# underground_cable_fault_finder.net
KiCad netlist of a schematic drawn in EAGLE
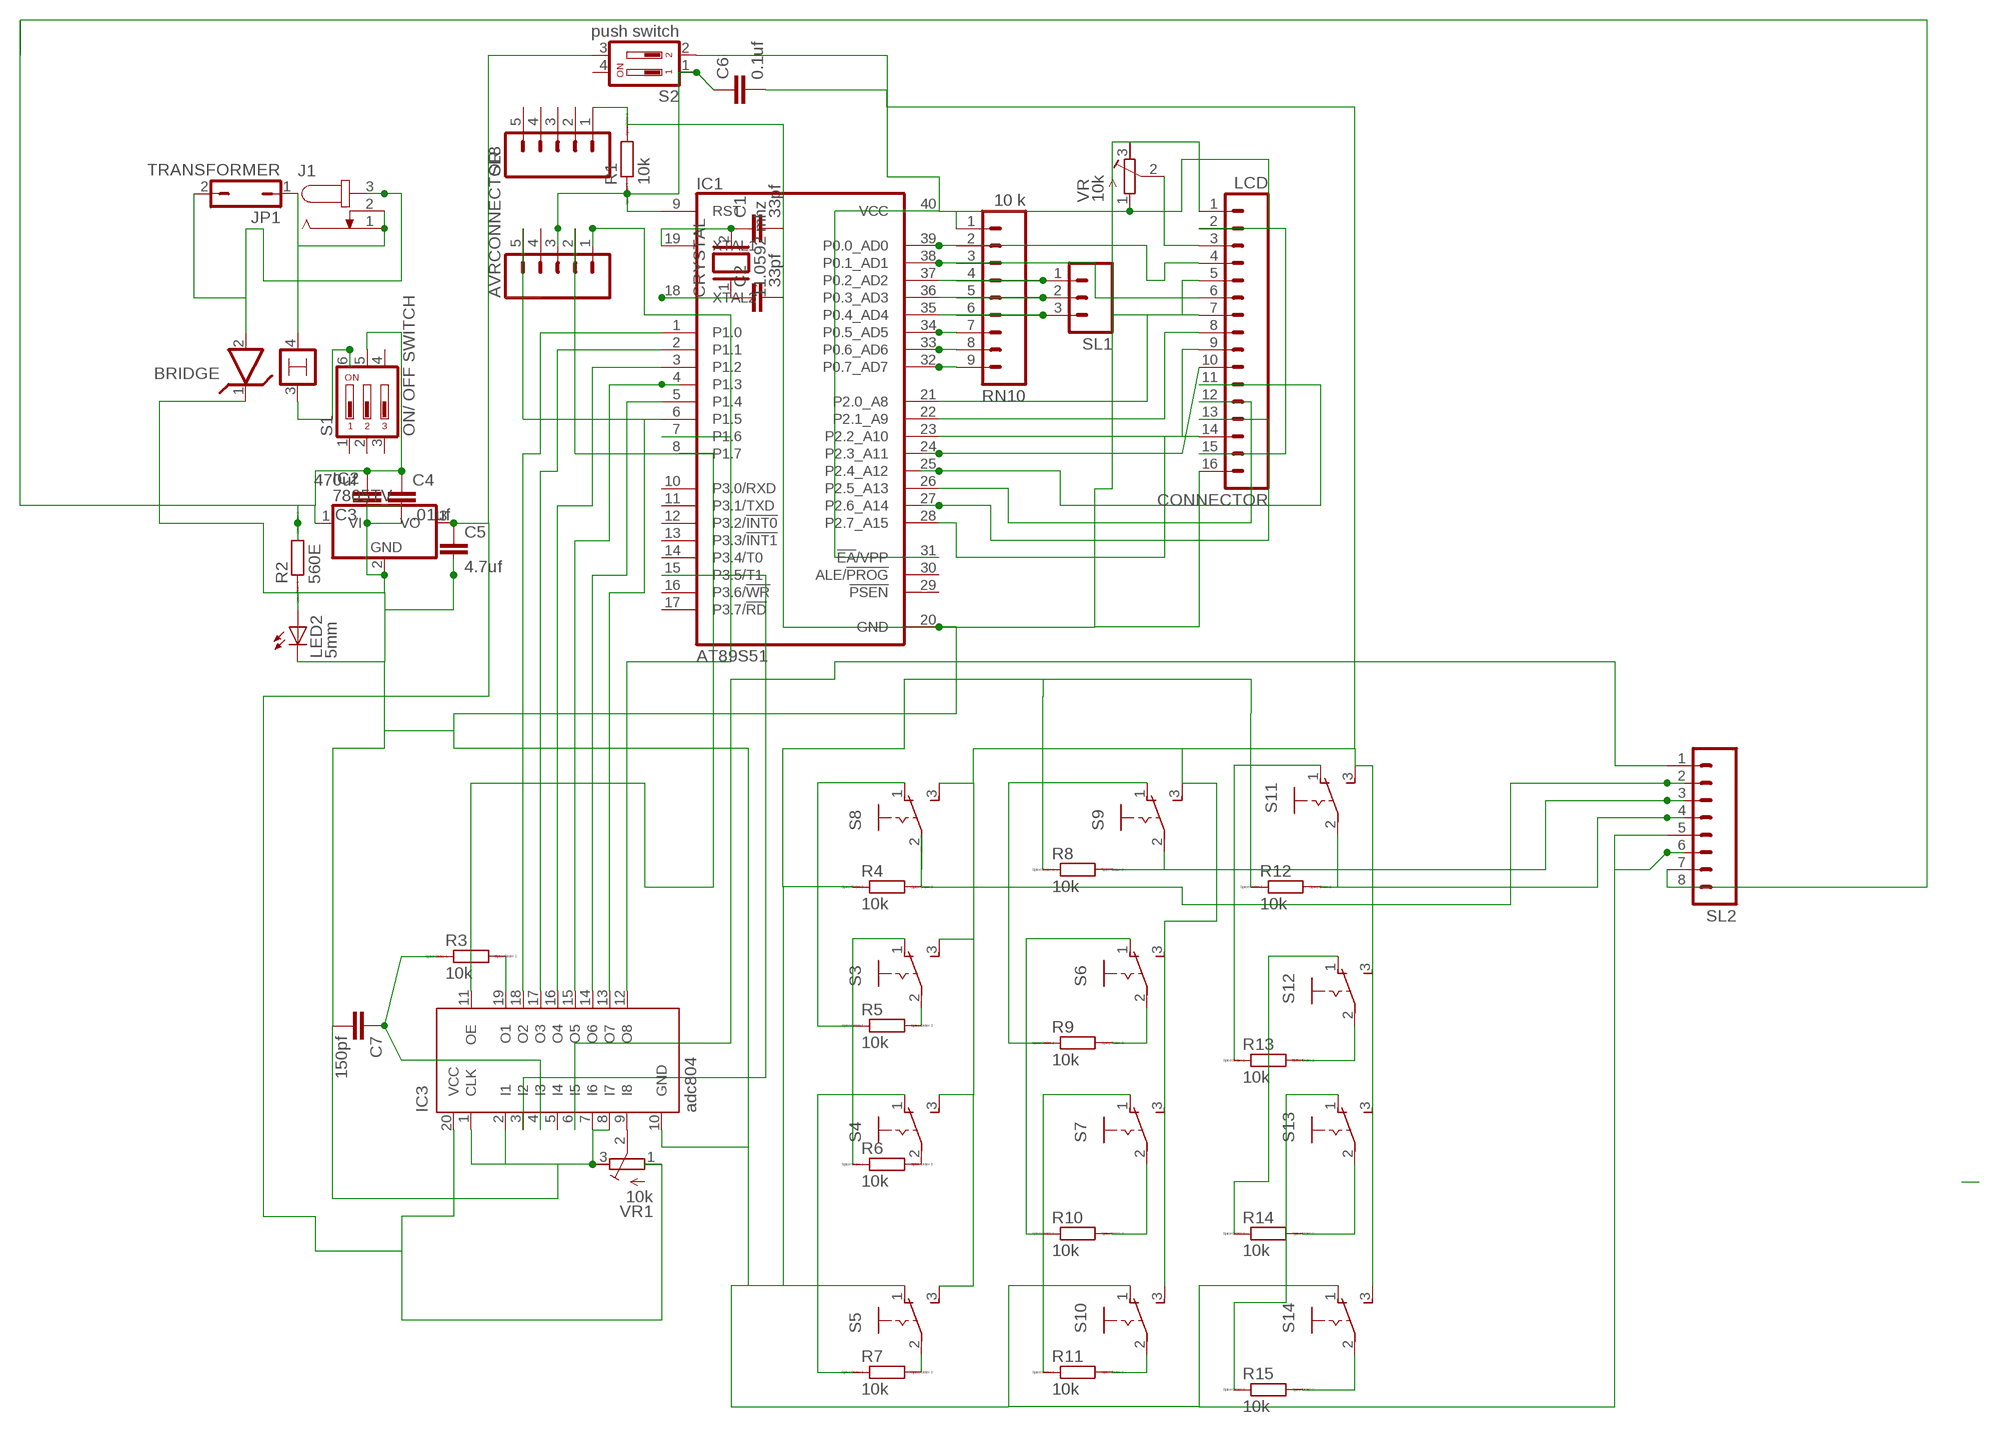
[diagram p0: schematic, sheet 1]

(export (version "E")
  (design (tool "Eeschema 10.0.6"))
  (components
    (comp (ref "AVRCONNECTOR")
      (value "M05")
      (footprint "eagle-import:05P")
      (libsource (lib "eagle-import") (part "M05"))
    )
    (comp (ref "BRIDGE")
      (value "LM399H")
      (footprint "eagle-import:TO39_4")
      (libsource (lib "eagle-import") (part "LM399H"))
    )
    (comp (ref "C1")
      (value "33pf")
      (footprint "eagle-import:C025-024X044")
      (libsource (lib "eagle-import") (part "C-EU025-024X044"))
    )
    (comp (ref "C2")
      (value "33pf")
      (footprint "eagle-import:C025-024X044")
      (libsource (lib "eagle-import") (part "C-EU025-024X044"))
    )
    (comp (ref "C3")
      (value "470uf")
      (footprint "eagle-import:C5B7.2")
      (libsource (lib "eagle-import") (part "C5/7.2"))
    )
    (comp (ref "C4")
      (value ".01uf")
      (footprint "eagle-import:C2.5-3")
      (libsource (lib "eagle-import") (part "C2,5-3"))
    )
    (comp (ref "C5")
      (value "4.7uf")
      (footprint "eagle-import:C2.5-3")
      (libsource (lib "eagle-import") (part "C2,5-3"))
    )
    (comp (ref "C6")
      (value "0.1uf")
      (footprint "eagle-import:C2.5-6")
      (libsource (lib "eagle-import") (part "C2.5/6"))
    )
    (comp (ref "C7")
      (value "150pf")
      (footprint "eagle-import:C2.5-3")
      (libsource (lib "eagle-import") (part "C2,5-3"))
    )
    (comp (ref "CONNECTOR")
      (value "LCD")
      (footprint "eagle-import:16P")
      (libsource (lib "eagle-import") (part "M16"))
    )
    (comp (ref "CRYSTAL")
      (value "11.0592 mhz")
      (footprint "eagle-import:QS")
      (libsource (lib "eagle-import") (part "XTAL/S"))
    )
    (comp (ref "IC1")
      (value "AT89S51")
      (footprint "eagle-import:DIL40")
      (libsource (lib "eagle-import") (part "AT89C51-PC12"))
    )
    (comp (ref "IC2")
      (value "7805TV")
      (footprint "eagle-import:TO220V")
      (libsource (lib "eagle-import") (part "78TV05"))
    )
    (comp (ref "IC3")
      (value "adc804")
      (footprint "eagle-import:DIL20")
      (fields (field (name "MPN") "ATF16V8CZ-15PU"))
      (libsource (lib "eagle-import") (part "ATF16V8BP3"))
    )
    (comp (ref "J1")
      (value "JACK-PLUG0")
      (footprint "eagle-import:SPC4077")
      (libsource (lib "eagle-import") (part "JACK-PLUG0"))
    )
    (comp (ref "JP1")
      (value "TRANSFORMER")
      (footprint "eagle-import:JP1")
      (libsource (lib "eagle-import") (part "JP1Q"))
    )
    (comp (ref "LED2")
      (value "5mm")
      (footprint "eagle-import:LED5MM")
      (libsource (lib "eagle-import") (part "LED5MM"))
    )
    (comp (ref "R1")
      (value "10k")
      (footprint "eagle-import:0204_7")
      (libsource (lib "eagle-import") (part "R0204/7"))
    )
    (comp (ref "R2")
      (value "560E")
      (footprint "eagle-import:0204_7")
      (libsource (lib "eagle-import") (part "R0204/7"))
    )
    (comp (ref "R3")
      (value "10k")
      (footprint "eagle-import:0204_7")
      (libsource (lib "eagle-import") (part "R0204/7"))
    )
    (comp (ref "R4")
      (value "10k")
      (footprint "eagle-import:0204_7")
      (fields (field (name "SPICEMODEL") "NONE") (field (name "SPICEPREFIX") "R"))
      (libsource (lib "eagle-import") (part "R0204/7"))
    )
    (comp (ref "R5")
      (value "10k")
      (footprint "eagle-import:0204_7")
      (fields (field (name "SPICEMODEL") "NONE") (field (name "SPICEPREFIX") "R"))
      (libsource (lib "eagle-import") (part "R0204/7"))
    )
    (comp (ref "R6")
      (value "10k")
      (footprint "eagle-import:0204_7")
      (fields (field (name "SPICEMODEL") "NONE") (field (name "SPICEPREFIX") "R"))
      (libsource (lib "eagle-import") (part "R0204/7"))
    )
    (comp (ref "R7")
      (value "10k")
      (footprint "eagle-import:0204_7")
      (fields (field (name "SPICEMODEL") "NONE") (field (name "SPICEPREFIX") "R"))
      (libsource (lib "eagle-import") (part "R0204/7"))
    )
    (comp (ref "R8")
      (value "10k")
      (footprint "eagle-import:0204_7")
      (fields (field (name "SPICEMODEL") "NONE") (field (name "SPICEPREFIX") "R"))
      (libsource (lib "eagle-import") (part "R0204/7"))
    )
    (comp (ref "R9")
      (value "10k")
      (footprint "eagle-import:0204_7")
      (fields (field (name "SPICEMODEL") "NONE") (field (name "SPICEPREFIX") "R"))
      (libsource (lib "eagle-import") (part "R0204/7"))
    )
    (comp (ref "R10")
      (value "10k")
      (footprint "eagle-import:0204_7")
      (fields (field (name "SPICEMODEL") "NONE") (field (name "SPICEPREFIX") "R"))
      (libsource (lib "eagle-import") (part "R0204/7"))
    )
    (comp (ref "R11")
      (value "10k")
      (footprint "eagle-import:0204_7")
      (fields (field (name "SPICEMODEL") "NONE") (field (name "SPICEPREFIX") "R"))
      (libsource (lib "eagle-import") (part "R0204/7"))
    )
    (comp (ref "R12")
      (value "10k")
      (footprint "eagle-import:0204_7")
      (fields (field (name "SPICEMODEL") "NONE") (field (name "SPICEPREFIX") "R"))
      (libsource (lib "eagle-import") (part "R0204/7"))
    )
    (comp (ref "R13")
      (value "10k")
      (footprint "eagle-import:0204_7")
      (fields (field (name "SPICEMODEL") "NONE") (field (name "SPICEPREFIX") "R"))
      (libsource (lib "eagle-import") (part "R0204/7"))
    )
    (comp (ref "R14")
      (value "10k")
      (footprint "eagle-import:0204_7")
      (fields (field (name "SPICEMODEL") "NONE") (field (name "SPICEPREFIX") "R"))
      (libsource (lib "eagle-import") (part "R0204/7"))
    )
    (comp (ref "R15")
      (value "10k")
      (footprint "eagle-import:0204_7")
      (fields (field (name "SPICEMODEL") "NONE") (field (name "SPICEPREFIX") "R"))
      (libsource (lib "eagle-import") (part "R0204/7"))
    )
    (comp (ref "RN10")
      (value "10 k")
      (footprint "eagle-import:09P")
      (libsource (lib "eagle-import") (part "M09"))
    )
    (comp (ref "S1")
      (value "ON/ OFF SWITCH")
      (footprint "eagle-import:DA-03")
      (fields (field (name "MPN") "MCDA03"))
      (libsource (lib "eagle-import") (part "DA03"))
    )
    (comp (ref "S2")
      (value "push switch")
      (footprint "eagle-import:DP-02")
      (fields (field (name "MPN") "MCDP02"))
      (libsource (lib "eagle-import") (part "DP02"))
    )
    (comp (ref "S3")
      (value "255SB")
      (footprint "eagle-import:255SB")
      (libsource (lib "eagle-import") (part "255SB"))
    )
    (comp (ref "S4")
      (value "255SB")
      (footprint "eagle-import:255SB")
      (libsource (lib "eagle-import") (part "255SB"))
    )
    (comp (ref "S5")
      (value "255SB")
      (footprint "eagle-import:255SB")
      (libsource (lib "eagle-import") (part "255SB"))
    )
    (comp (ref "S6")
      (value "255SB")
      (footprint "eagle-import:255SB")
      (libsource (lib "eagle-import") (part "255SB"))
    )
    (comp (ref "S7")
      (value "255SB")
      (footprint "eagle-import:255SB")
      (libsource (lib "eagle-import") (part "255SB"))
    )
    (comp (ref "S8")
      (value "255SB")
      (footprint "eagle-import:255SB")
      (libsource (lib "eagle-import") (part "255SB"))
    )
    (comp (ref "S9")
      (value "255SB")
      (footprint "eagle-import:255SB")
      (libsource (lib "eagle-import") (part "255SB"))
    )
    (comp (ref "S10")
      (value "255SB")
      (footprint "eagle-import:255SB")
      (libsource (lib "eagle-import") (part "255SB"))
    )
    (comp (ref "S11")
      (value "255SB")
      (footprint "eagle-import:255SB")
      (libsource (lib "eagle-import") (part "255SB"))
    )
    (comp (ref "S12")
      (value "255SB")
      (footprint "eagle-import:255SB")
      (libsource (lib "eagle-import") (part "255SB"))
    )
    (comp (ref "S13")
      (value "255SB")
      (footprint "eagle-import:255SB")
      (libsource (lib "eagle-import") (part "255SB"))
    )
    (comp (ref "S14")
      (value "255SB")
      (footprint "eagle-import:255SB")
      (libsource (lib "eagle-import") (part "255SB"))
    )
    (comp (ref "SL1")
      (value "M03")
      (footprint "eagle-import:03P")
      (libsource (lib "eagle-import") (part "M03"))
    )
    (comp (ref "SL2")
      (value "M08")
      (footprint "eagle-import:08P")
      (libsource (lib "eagle-import") (part "M08"))
    )
    (comp (ref "SL8")
      (value "M05")
      (footprint "eagle-import:05P")
      (libsource (lib "eagle-import") (part "M05"))
    )
    (comp (ref "VR")
      (value "10k")
      (footprint "eagle-import:RTRIM64P")
      (libsource (lib "eagle-import") (part "R-TRIMM64P"))
    )
    (comp (ref "VR1")
      (value "10k")
      (footprint "eagle-import:RTRIM64P")
      (libsource (lib "eagle-import") (part "R-TRIMM64P"))
    )
  )
  (nets
    (net (code "1") (name "Net-(BRIDGE-Pad2)") (class "Default")
      (node (ref "BRIDGE") (pin "2") (pinfunction "2_2") (pintype "input"))
      (node (ref "J1") (pin "3") (pinfunction "3_3") (pintype "passive"))
      (node (ref "JP1") (pin "2") (pinfunction "2_2") (pintype "passive"))
    )
    (net (code "2") (name "Net-(BRIDGE-Pad3)") (class "Default")
      (node (ref "BRIDGE") (pin "3") (pinfunction "3_3") (pintype "input"))
      (node (ref "S1") (pin "6") (pinfunction "6_6") (pintype "passive"))
    )
    (net (code "3") (name "Net-(BRIDGE-Pad4)") (class "Default")
      (node (ref "BRIDGE") (pin "4") (pinfunction "4_4") (pintype "input"))
      (node (ref "J1") (pin "1") (pinfunction "1_1") (pintype "passive"))
      (node (ref "J1") (pin "2") (pinfunction "2_2") (pintype "passive"))
      (node (ref "JP1") (pin "1") (pinfunction "1_1") (pintype "passive"))
    )
    (net (code "4") (name "Net-(IC1-GND)") (class "Default")
      (node (ref "BRIDGE") (pin "1") (pinfunction "1_1") (pintype "input"))
      (node (ref "C1") (pin "2") (pinfunction "2_2") (pintype "passive"))
      (node (ref "C2") (pin "2") (pinfunction "2_2") (pintype "passive"))
      (node (ref "C3") (pin "1") (pinfunction "1_1") (pintype "passive"))
      (node (ref "C4") (pin "2") (pinfunction "2_2") (pintype "passive"))
      (node (ref "C5") (pin "2") (pinfunction "2_2") (pintype "passive"))
      (node (ref "C7") (pin "2") (pinfunction "2_2") (pintype "passive"))
      (node (ref "CONNECTOR") (pin "1") (pinfunction "1_1") (pintype "passive"))
      (node (ref "CONNECTOR") (pin "16") (pinfunction "16_16") (pintype "passive"))
      (node (ref "CONNECTOR") (pin "5") (pinfunction "5_5") (pintype "passive"))
      (node (ref "IC1") (pin "20") (pinfunction "GND_20") (pintype "power_in"))
      (node (ref "IC2") (pin "2") (pinfunction "GND_2") (pintype "passive"))
      (node (ref "IC3") (pin "1") (pinfunction "CLK_1") (pintype "input"))
      (node (ref "IC3") (pin "10") (pinfunction "GND_10") (pintype "power_in"))
      (node (ref "IC3") (pin "2") (pinfunction "I1_2") (pintype "input"))
      (node (ref "IC3") (pin "7") (pinfunction "I6_7") (pintype "input"))
      (node (ref "IC3") (pin "8") (pinfunction "I7_8") (pintype "input"))
      (node (ref "LED2") (pin "K") (pinfunction "C_K") (pintype "passive"))
      (node (ref "R1") (pin "2") (pinfunction "2_2") (pintype "passive"))
      (node (ref "R12") (pin "1") (pinfunction "1_1") (pintype "passive"))
      (node (ref "R4") (pin "1") (pinfunction "1_1") (pintype "passive"))
      (node (ref "R8") (pin "1") (pinfunction "1_1") (pintype "passive"))
      (node (ref "S10") (pin "1") (pinfunction "O_1") (pintype "passive"))
      (node (ref "S14") (pin "1") (pinfunction "O_1") (pintype "passive"))
      (node (ref "S5") (pin "1") (pinfunction "O_1") (pintype "passive"))
      (node (ref "SL2") (pin "5") (pinfunction "5_5") (pintype "passive"))
      (node (ref "SL2") (pin "6") (pinfunction "6_6") (pintype "passive"))
      (node (ref "SL8") (pin "1") (pinfunction "1_1") (pintype "passive"))
      (node (ref "VR") (pin "3") (pinfunction "A_3") (pintype "passive"))
      (node (ref "VR1") (pin "3") (pinfunction "A_3") (pintype "passive"))
    )
    (net (code "5") (name "Net-(IC1-P0.0_AD0)") (class "Default")
      (node (ref "CONNECTOR") (pin "4") (pinfunction "4_4") (pintype "passive"))
      (node (ref "IC1") (pin "39") (pinfunction "P0.0_AD0_39") (pintype "bidirectional"))
      (node (ref "RN10") (pin "2") (pinfunction "2_2") (pintype "passive"))
    )
    (net (code "6") (name "Net-(IC1-P0.1_AD1)") (class "Default")
      (node (ref "CONNECTOR") (pin "6") (pinfunction "6_6") (pintype "passive"))
      (node (ref "IC1") (pin "38") (pinfunction "P0.1_AD1_38") (pintype "bidirectional"))
      (node (ref "RN10") (pin "3") (pinfunction "3_3") (pintype "passive"))
    )
    (net (code "7") (name "Net-(IC1-P0.2_AD2)") (class "Default")
      (node (ref "IC1") (pin "37") (pinfunction "P0.2_AD2_37") (pintype "bidirectional"))
      (node (ref "RN10") (pin "4") (pinfunction "4_4") (pintype "passive"))
      (node (ref "SL1") (pin "1") (pinfunction "1_1") (pintype "passive"))
    )
    (net (code "8") (name "Net-(IC1-P0.3_AD3)") (class "Default")
      (node (ref "IC1") (pin "36") (pinfunction "P0.3_AD3_36") (pintype "bidirectional"))
      (node (ref "RN10") (pin "5") (pinfunction "5_5") (pintype "passive"))
      (node (ref "SL1") (pin "2") (pinfunction "2_2") (pintype "passive"))
    )
    (net (code "9") (name "Net-(IC1-P0.4_AD4)") (class "Default")
      (node (ref "IC1") (pin "35") (pinfunction "P0.4_AD4_35") (pintype "bidirectional"))
      (node (ref "RN10") (pin "6") (pinfunction "6_6") (pintype "passive"))
      (node (ref "SL1") (pin "3") (pinfunction "3_3") (pintype "passive"))
    )
    (net (code "10") (name "Net-(IC1-P0.5_AD5)") (class "Default")
      (node (ref "IC1") (pin "34") (pinfunction "P0.5_AD5_34") (pintype "bidirectional"))
      (node (ref "RN10") (pin "7") (pinfunction "7_7") (pintype "passive"))
    )
    (net (code "11") (name "Net-(IC1-P0.6_AD6)") (class "Default")
      (node (ref "IC1") (pin "33") (pinfunction "P0.6_AD6_33") (pintype "bidirectional"))
      (node (ref "RN10") (pin "8") (pinfunction "8_8") (pintype "passive"))
    )
    (net (code "12") (name "Net-(IC1-P0.7_AD7)") (class "Default")
      (node (ref "IC1") (pin "32") (pinfunction "P0.7_AD7_32") (pintype "bidirectional"))
      (node (ref "RN10") (pin "9") (pinfunction "9_9") (pintype "passive"))
    )
    (net (code "13") (name "Net-(IC1-P1.0)") (class "Default")
      (node (ref "IC1") (pin "1") (pinfunction "P1.0_1") (pintype "bidirectional"))
      (node (ref "IC3") (pin "18") (pinfunction "O2_18") (pintype "output"))
    )
    (net (code "14") (name "Net-(IC1-P1.1)") (class "Default")
      (node (ref "IC1") (pin "2") (pinfunction "P1.1_2") (pintype "bidirectional"))
      (node (ref "IC3") (pin "17") (pinfunction "O3_17") (pintype "output"))
    )
    (net (code "15") (name "Net-(IC1-P1.2)") (class "Default")
      (node (ref "IC1") (pin "3") (pinfunction "P1.2_3") (pintype "bidirectional"))
      (node (ref "IC3") (pin "16") (pinfunction "O4_16") (pintype "output"))
    )
    (net (code "16") (name "Net-(IC1-P1.3)") (class "Default")
      (node (ref "IC1") (pin "4") (pinfunction "P1.3_4") (pintype "bidirectional"))
      (node (ref "IC3") (pin "15") (pinfunction "O5_15") (pintype "output"))
    )
    (net (code "17") (name "Net-(IC1-P1.4)") (class "Default")
      (node (ref "IC1") (pin "5") (pinfunction "P1.4_5") (pintype "bidirectional"))
      (node (ref "IC3") (pin "14") (pinfunction "O6_14") (pintype "output"))
    )
    (net (code "18") (name "Net-(IC1-P1.5)") (class "Default")
      (node (ref "AVRCONNECTOR") (pin "5") (pinfunction "5_5") (pintype "passive"))
      (node (ref "IC1") (pin "6") (pinfunction "P1.5_6") (pintype "bidirectional"))
      (node (ref "IC3") (pin "13") (pinfunction "O7_13") (pintype "output"))
    )
    (net (code "19") (name "Net-(IC1-P1.6)") (class "Default")
      (node (ref "AVRCONNECTOR") (pin "1") (pinfunction "1_1") (pintype "passive"))
      (node (ref "IC1") (pin "7") (pinfunction "P1.6_7") (pintype "bidirectional"))
      (node (ref "IC3") (pin "12") (pinfunction "O8_12") (pintype "output"))
    )
    (net (code "20") (name "Net-(IC1-P1.7)") (class "Default")
      (node (ref "AVRCONNECTOR") (pin "2") (pinfunction "2_2") (pintype "passive"))
      (node (ref "IC1") (pin "8") (pinfunction "P1.7_8") (pintype "bidirectional"))
      (node (ref "IC3") (pin "11") (pinfunction "OE_11") (pintype "input"))
    )
    (net (code "21") (name "Net-(IC1-P2.0_A8)") (class "Default")
      (node (ref "CONNECTOR") (pin "7") (pinfunction "7_7") (pintype "passive"))
      (node (ref "IC1") (pin "21") (pinfunction "P2.0_A8_21") (pintype "bidirectional"))
    )
    (net (code "22") (name "Net-(IC1-P2.1_A9)") (class "Default")
      (node (ref "CONNECTOR") (pin "8") (pinfunction "8_8") (pintype "passive"))
      (node (ref "IC1") (pin "22") (pinfunction "P2.1_A9_22") (pintype "bidirectional"))
    )
    (net (code "23") (name "Net-(IC1-P2.2_A10)") (class "Default")
      (node (ref "CONNECTOR") (pin "9") (pinfunction "9_9") (pintype "passive"))
      (node (ref "IC1") (pin "23") (pinfunction "P2.2_A10_23") (pintype "bidirectional"))
    )
    (net (code "24") (name "Net-(IC1-P2.3_A11)") (class "Default")
      (node (ref "CONNECTOR") (pin "10") (pinfunction "10_10") (pintype "passive"))
      (node (ref "IC1") (pin "24") (pinfunction "P2.3_A11_24") (pintype "bidirectional"))
    )
    (net (code "25") (name "Net-(IC1-P2.4_A12)") (class "Default")
      (node (ref "CONNECTOR") (pin "11") (pinfunction "11_11") (pintype "passive"))
      (node (ref "IC1") (pin "25") (pinfunction "P2.4_A12_25") (pintype "bidirectional"))
    )
    (net (code "26") (name "Net-(IC1-P2.5_A13)") (class "Default")
      (node (ref "CONNECTOR") (pin "12") (pinfunction "12_12") (pintype "passive"))
      (node (ref "IC1") (pin "26") (pinfunction "P2.5_A13_26") (pintype "bidirectional"))
    )
    (net (code "27") (name "Net-(IC1-P2.6_A14)") (class "Default")
      (node (ref "CONNECTOR") (pin "13") (pinfunction "13_13") (pintype "passive"))
      (node (ref "IC1") (pin "27") (pinfunction "P2.6_A14_27") (pintype "bidirectional"))
    )
    (net (code "28") (name "Net-(IC1-P2.7_A15)") (class "Default")
      (node (ref "CONNECTOR") (pin "14") (pinfunction "14_14") (pintype "passive"))
      (node (ref "IC1") (pin "28") (pinfunction "P2.7_A15_28") (pintype "bidirectional"))
    )
    (net (code "29") (name "Net-(IC1-P3.5{slash}T1)") (class "Default")
      (node (ref "IC1") (pin "15") (pinfunction "P3.5/T1_15") (pintype "bidirectional"))
      (node (ref "IC3") (pin "3") (pinfunction "I2_3") (pintype "input"))
    )
    (net (code "30") (name "Net-(IC1-RST)") (class "Default")
      (node (ref "AVRCONNECTOR") (pin "3") (pinfunction "3_3") (pintype "passive"))
      (node (ref "C6") (pin "1") (pinfunction "1_1") (pintype "passive"))
      (node (ref "IC1") (pin "9") (pinfunction "RST_9") (pintype "input"))
      (node (ref "R1") (pin "1") (pinfunction "1_1") (pintype "passive"))
      (node (ref "S2") (pin "1") (pinfunction "1_1") (pintype "passive"))
    )
    (net (code "31") (name "Net-(IC1-VCC)") (class "Default")
      (node (ref "C6") (pin "2") (pinfunction "2_2") (pintype "passive"))
      (node (ref "CONNECTOR") (pin "15") (pinfunction "15_15") (pintype "passive"))
      (node (ref "CONNECTOR") (pin "2") (pinfunction "2_2") (pintype "passive"))
      (node (ref "IC1") (pin "31") (pinfunction "~{EA}/VPP_31") (pintype "input"))
      (node (ref "IC1") (pin "40") (pinfunction "VCC_40") (pintype "power_in"))
      (node (ref "RN10") (pin "1") (pinfunction "1_1") (pintype "passive"))
      (node (ref "S10") (pin "3") (pinfunction "S_3") (pintype "passive"))
      (node (ref "S11") (pin "3") (pinfunction "S_3") (pintype "passive"))
      (node (ref "S12") (pin "3") (pinfunction "S_3") (pintype "passive"))
      (node (ref "S13") (pin "3") (pinfunction "S_3") (pintype "passive"))
      (node (ref "S14") (pin "3") (pinfunction "S_3") (pintype "passive"))
      (node (ref "S2") (pin "2") (pinfunction "2_2") (pintype "passive"))
      (node (ref "S3") (pin "3") (pinfunction "S_3") (pintype "passive"))
      (node (ref "S4") (pin "3") (pinfunction "S_3") (pintype "passive"))
      (node (ref "S5") (pin "3") (pinfunction "S_3") (pintype "passive"))
      (node (ref "S6") (pin "3") (pinfunction "S_3") (pintype "passive"))
      (node (ref "S7") (pin "3") (pinfunction "S_3") (pintype "passive"))
      (node (ref "S8") (pin "3") (pinfunction "S_3") (pintype "passive"))
      (node (ref "S9") (pin "3") (pinfunction "S_3") (pintype "passive"))
      (node (ref "VR") (pin "1") (pinfunction "E_1") (pintype "passive"))
    )
    (net (code "32") (name "Net-(IC1-XTAL1)") (class "Default")
      (node (ref "C1") (pin "1") (pinfunction "1_1") (pintype "passive"))
      (node (ref "CRYSTAL") (pin "2") (pinfunction "2_2") (pintype "passive"))
      (node (ref "IC1") (pin "19") (pinfunction "XTAL1_19") (pintype "input"))
    )
    (net (code "33") (name "Net-(IC1-XTAL2)") (class "Default")
      (node (ref "C2") (pin "1") (pinfunction "1_1") (pintype "passive"))
      (node (ref "CRYSTAL") (pin "1") (pinfunction "1_1") (pintype "passive"))
      (node (ref "IC1") (pin "18") (pinfunction "XTAL2_18") (pintype "input"))
    )
    (net (code "34") (name "Net-(IC2-VI)") (class "Default")
      (node (ref "C3") (pin "2") (pinfunction "2_2") (pintype "passive"))
      (node (ref "C4") (pin "1") (pinfunction "1_1") (pintype "passive"))
      (node (ref "IC2") (pin "1") (pinfunction "VI_1") (pintype "input"))
      (node (ref "R2") (pin "2") (pinfunction "2_2") (pintype "passive"))
      (node (ref "S1") (pin "5") (pinfunction "5_5") (pintype "passive"))
      (node (ref "SL2") (pin "7") (pinfunction "7_7") (pintype "passive"))
      (node (ref "SL2") (pin "8") (pinfunction "8_8") (pintype "passive"))
    )
    (net (code "35") (name "Net-(IC2-VO)") (class "Default")
      (node (ref "C5") (pin "1") (pinfunction "1_1") (pintype "passive"))
      (node (ref "IC2") (pin "3") (pinfunction "VO_3") (pintype "passive"))
      (node (ref "IC3") (pin "20") (pinfunction "VCC_20") (pintype "power_in"))
      (node (ref "S2") (pin "3") (pinfunction "3_3") (pintype "passive"))
      (node (ref "VR1") (pin "1") (pinfunction "E_1") (pintype "passive"))
    )
    (net (code "36") (name "Net-(IC3-I3)") (class "Default")
      (node (ref "C7") (pin "1") (pinfunction "1_1") (pintype "passive"))
      (node (ref "IC3") (pin "4") (pinfunction "I3_4") (pintype "input"))
      (node (ref "R3") (pin "1") (pinfunction "1_1") (pintype "passive"))
    )
    (net (code "37") (name "Net-(IC3-I5)") (class "Default")
      (node (ref "IC3") (pin "6") (pinfunction "I5_6") (pintype "input"))
      (node (ref "SL2") (pin "1") (pinfunction "1_1") (pintype "passive"))
    )
    (net (code "38") (name "Net-(IC3-I8)") (class "Default")
      (node (ref "IC3") (pin "9") (pinfunction "I8_9") (pintype "input"))
      (node (ref "VR1") (pin "2") (pinfunction "S_2") (pintype "passive"))
    )
    (net (code "39") (name "Net-(IC3-O1)") (class "Default")
      (node (ref "IC3") (pin "19") (pinfunction "O1_19") (pintype "output"))
      (node (ref "R3") (pin "2") (pinfunction "2_2") (pintype "passive"))
    )
    (net (code "40") (name "Net-(LED2-PadA)") (class "Default")
      (node (ref "LED2") (pin "A") (pinfunction "A_A") (pintype "passive"))
      (node (ref "R2") (pin "1") (pinfunction "1_1") (pintype "passive"))
    )
    (net (code "41") (name "Net-(S3-O)") (class "Default")
      (node (ref "R6") (pin "1") (pinfunction "1_1") (pintype "passive"))
      (node (ref "S3") (pin "1") (pinfunction "O_1") (pintype "passive"))
    )
    (net (code "42") (name "Net-(S3-P)") (class "Default")
      (node (ref "R5") (pin "2") (pinfunction "2_2") (pintype "passive"))
      (node (ref "S3") (pin "2") (pinfunction "P_2") (pintype "passive"))
    )
    (net (code "43") (name "Net-(S4-O)") (class "Default")
      (node (ref "R7") (pin "1") (pinfunction "1_1") (pintype "passive"))
      (node (ref "S4") (pin "1") (pinfunction "O_1") (pintype "passive"))
    )
    (net (code "44") (name "Net-(S4-P)") (class "Default")
      (node (ref "R6") (pin "2") (pinfunction "2_2") (pintype "passive"))
      (node (ref "S4") (pin "2") (pinfunction "P_2") (pintype "passive"))
    )
    (net (code "45") (name "Net-(S5-P)") (class "Default")
      (node (ref "R7") (pin "2") (pinfunction "2_2") (pintype "passive"))
      (node (ref "S5") (pin "2") (pinfunction "P_2") (pintype "passive"))
    )
    (net (code "46") (name "Net-(S6-O)") (class "Default")
      (node (ref "R10") (pin "1") (pinfunction "1_1") (pintype "passive"))
      (node (ref "S6") (pin "1") (pinfunction "O_1") (pintype "passive"))
    )
    (net (code "47") (name "Net-(S6-P)") (class "Default")
      (node (ref "R9") (pin "2") (pinfunction "2_2") (pintype "passive"))
      (node (ref "S6") (pin "2") (pinfunction "P_2") (pintype "passive"))
    )
    (net (code "48") (name "Net-(S7-O)") (class "Default")
      (node (ref "R11") (pin "1") (pinfunction "1_1") (pintype "passive"))
      (node (ref "S7") (pin "1") (pinfunction "O_1") (pintype "passive"))
    )
    (net (code "49") (name "Net-(S7-P)") (class "Default")
      (node (ref "R10") (pin "2") (pinfunction "2_2") (pintype "passive"))
      (node (ref "S7") (pin "2") (pinfunction "P_2") (pintype "passive"))
    )
    (net (code "50") (name "Net-(S8-O)") (class "Default")
      (node (ref "R5") (pin "1") (pinfunction "1_1") (pintype "passive"))
      (node (ref "S8") (pin "1") (pinfunction "O_1") (pintype "passive"))
    )
    (net (code "51") (name "Net-(S8-P)") (class "Default")
      (node (ref "R4") (pin "2") (pinfunction "2_2") (pintype "passive"))
      (node (ref "S8") (pin "2") (pinfunction "P_2") (pintype "passive"))
      (node (ref "SL2") (pin "2") (pinfunction "2_2") (pintype "passive"))
    )
    (net (code "52") (name "Net-(S9-O)") (class "Default")
      (node (ref "R9") (pin "1") (pinfunction "1_1") (pintype "passive"))
      (node (ref "S9") (pin "1") (pinfunction "O_1") (pintype "passive"))
    )
    (net (code "53") (name "Net-(S9-P)") (class "Default")
      (node (ref "R8") (pin "2") (pinfunction "2_2") (pintype "passive"))
      (node (ref "S9") (pin "2") (pinfunction "P_2") (pintype "passive"))
      (node (ref "SL2") (pin "3") (pinfunction "3_3") (pintype "passive"))
    )
    (net (code "54") (name "Net-(S10-P)") (class "Default")
      (node (ref "R11") (pin "2") (pinfunction "2_2") (pintype "passive"))
      (node (ref "S10") (pin "2") (pinfunction "P_2") (pintype "passive"))
    )
    (net (code "55") (name "Net-(S11-O)") (class "Default")
      (node (ref "R13") (pin "1") (pinfunction "1_1") (pintype "passive"))
      (node (ref "S11") (pin "1") (pinfunction "O_1") (pintype "passive"))
    )
    (net (code "56") (name "Net-(S11-P)") (class "Default")
      (node (ref "R12") (pin "2") (pinfunction "2_2") (pintype "passive"))
      (node (ref "S11") (pin "2") (pinfunction "P_2") (pintype "passive"))
      (node (ref "SL2") (pin "4") (pinfunction "4_4") (pintype "passive"))
    )
    (net (code "57") (name "Net-(S12-O)") (class "Default")
      (node (ref "R14") (pin "1") (pinfunction "1_1") (pintype "passive"))
      (node (ref "S12") (pin "1") (pinfunction "O_1") (pintype "passive"))
    )
    (net (code "58") (name "Net-(S12-P)") (class "Default")
      (node (ref "R13") (pin "2") (pinfunction "2_2") (pintype "passive"))
      (node (ref "S12") (pin "2") (pinfunction "P_2") (pintype "passive"))
    )
    (net (code "59") (name "Net-(S13-O)") (class "Default")
      (node (ref "R15") (pin "1") (pinfunction "1_1") (pintype "passive"))
      (node (ref "S13") (pin "1") (pinfunction "O_1") (pintype "passive"))
    )
    (net (code "60") (name "Net-(S13-P)") (class "Default")
      (node (ref "R14") (pin "2") (pinfunction "2_2") (pintype "passive"))
      (node (ref "S13") (pin "2") (pinfunction "P_2") (pintype "passive"))
    )
    (net (code "61") (name "Net-(S14-P)") (class "Default")
      (node (ref "R15") (pin "2") (pinfunction "2_2") (pintype "passive"))
      (node (ref "S14") (pin "2") (pinfunction "P_2") (pintype "passive"))
    )
    (net (code "62") (name "Net-(VR-S)") (class "Default")
      (node (ref "CONNECTOR") (pin "3") (pinfunction "3_3") (pintype "passive"))
      (node (ref "VR") (pin "2") (pinfunction "S_2") (pintype "passive"))
    )
    (net (code "63") (name "unconnected-(AVRCONNECTOR-Pad4)") (class "Default")
      (node (ref "AVRCONNECTOR") (pin "4") (pinfunction "4_4") (pintype "passive"))
    )
    (net (code "64") (name "unconnected-(IC1-ALE{slash}~{PROG}-Pad30)") (class "Default")
      (node (ref "IC1") (pin "30") (pinfunction "ALE/~{PROG}_30") (pintype "output"))
    )
    (net (code "65") (name "unconnected-(IC1-P3.0{slash}RXD-Pad10)") (class "Default")
      (node (ref "IC1") (pin "10") (pinfunction "P3.0/RXD_10") (pintype "bidirectional"))
    )
    (net (code "66") (name "unconnected-(IC1-P3.1{slash}TXD-Pad11)") (class "Default")
      (node (ref "IC1") (pin "11") (pinfunction "P3.1/TXD_11") (pintype "bidirectional"))
    )
    (net (code "67") (name "unconnected-(IC1-P3.2{slash}~{INT0}-Pad12)") (class "Default")
      (node (ref "IC1") (pin "12") (pinfunction "P3.2/~{INT0}_12") (pintype "bidirectional"))
    )
    (net (code "68") (name "unconnected-(IC1-P3.3{slash}~{INT1}-Pad13)") (class "Default")
      (node (ref "IC1") (pin "13") (pinfunction "P3.3/~{INT1}_13") (pintype "bidirectional"))
    )
    (net (code "69") (name "unconnected-(IC1-P3.4{slash}T0-Pad14)") (class "Default")
      (node (ref "IC1") (pin "14") (pinfunction "P3.4/T0_14") (pintype "bidirectional"))
    )
    (net (code "70") (name "unconnected-(IC1-P3.6{slash}~{WR}-Pad16)") (class "Default")
      (node (ref "IC1") (pin "16") (pinfunction "P3.6/~{WR}_16") (pintype "bidirectional"))
    )
    (net (code "71") (name "unconnected-(IC1-P3.7{slash}~{RD}-Pad17)") (class "Default")
      (node (ref "IC1") (pin "17") (pinfunction "P3.7/~{RD}_17") (pintype "bidirectional"))
    )
    (net (code "72") (name "unconnected-(IC1-~{PSEN}-Pad29)") (class "Default")
      (node (ref "IC1") (pin "29") (pinfunction "~{PSEN}_29") (pintype "output"))
    )
    (net (code "73") (name "unconnected-(IC3-I4-Pad5)") (class "Default")
      (node (ref "IC3") (pin "5") (pinfunction "I4_5") (pintype "input"))
    )
    (net (code "74") (name "unconnected-(S1-Pad1)") (class "Default")
      (node (ref "S1") (pin "1") (pinfunction "1_1") (pintype "passive"))
    )
    (net (code "75") (name "unconnected-(S1-Pad2)") (class "Default")
      (node (ref "S1") (pin "2") (pinfunction "2_2") (pintype "passive"))
    )
    (net (code "76") (name "unconnected-(S1-Pad3)") (class "Default")
      (node (ref "S1") (pin "3") (pinfunction "3_3") (pintype "passive"))
    )
    (net (code "77") (name "unconnected-(S1-Pad4)") (class "Default")
      (node (ref "S1") (pin "4") (pinfunction "4_4") (pintype "passive"))
    )
    (net (code "78") (name "unconnected-(S2-Pad4)") (class "Default")
      (node (ref "S2") (pin "4") (pinfunction "4_4") (pintype "passive"))
    )
    (net (code "79") (name "unconnected-(SL8-Pad2)") (class "Default")
      (node (ref "SL8") (pin "2") (pinfunction "2_2") (pintype "passive"))
    )
    (net (code "80") (name "unconnected-(SL8-Pad3)") (class "Default")
      (node (ref "SL8") (pin "3") (pinfunction "3_3") (pintype "passive"))
    )
    (net (code "81") (name "unconnected-(SL8-Pad4)") (class "Default")
      (node (ref "SL8") (pin "4") (pinfunction "4_4") (pintype "passive"))
    )
    (net (code "82") (name "unconnected-(SL8-Pad5)") (class "Default")
      (node (ref "SL8") (pin "5") (pinfunction "5_5") (pintype "passive"))
    )
  )
)
